# Robot_Psoc_Caras_2_2.net
KiCad netlist of a schematic drawn in EAGLE
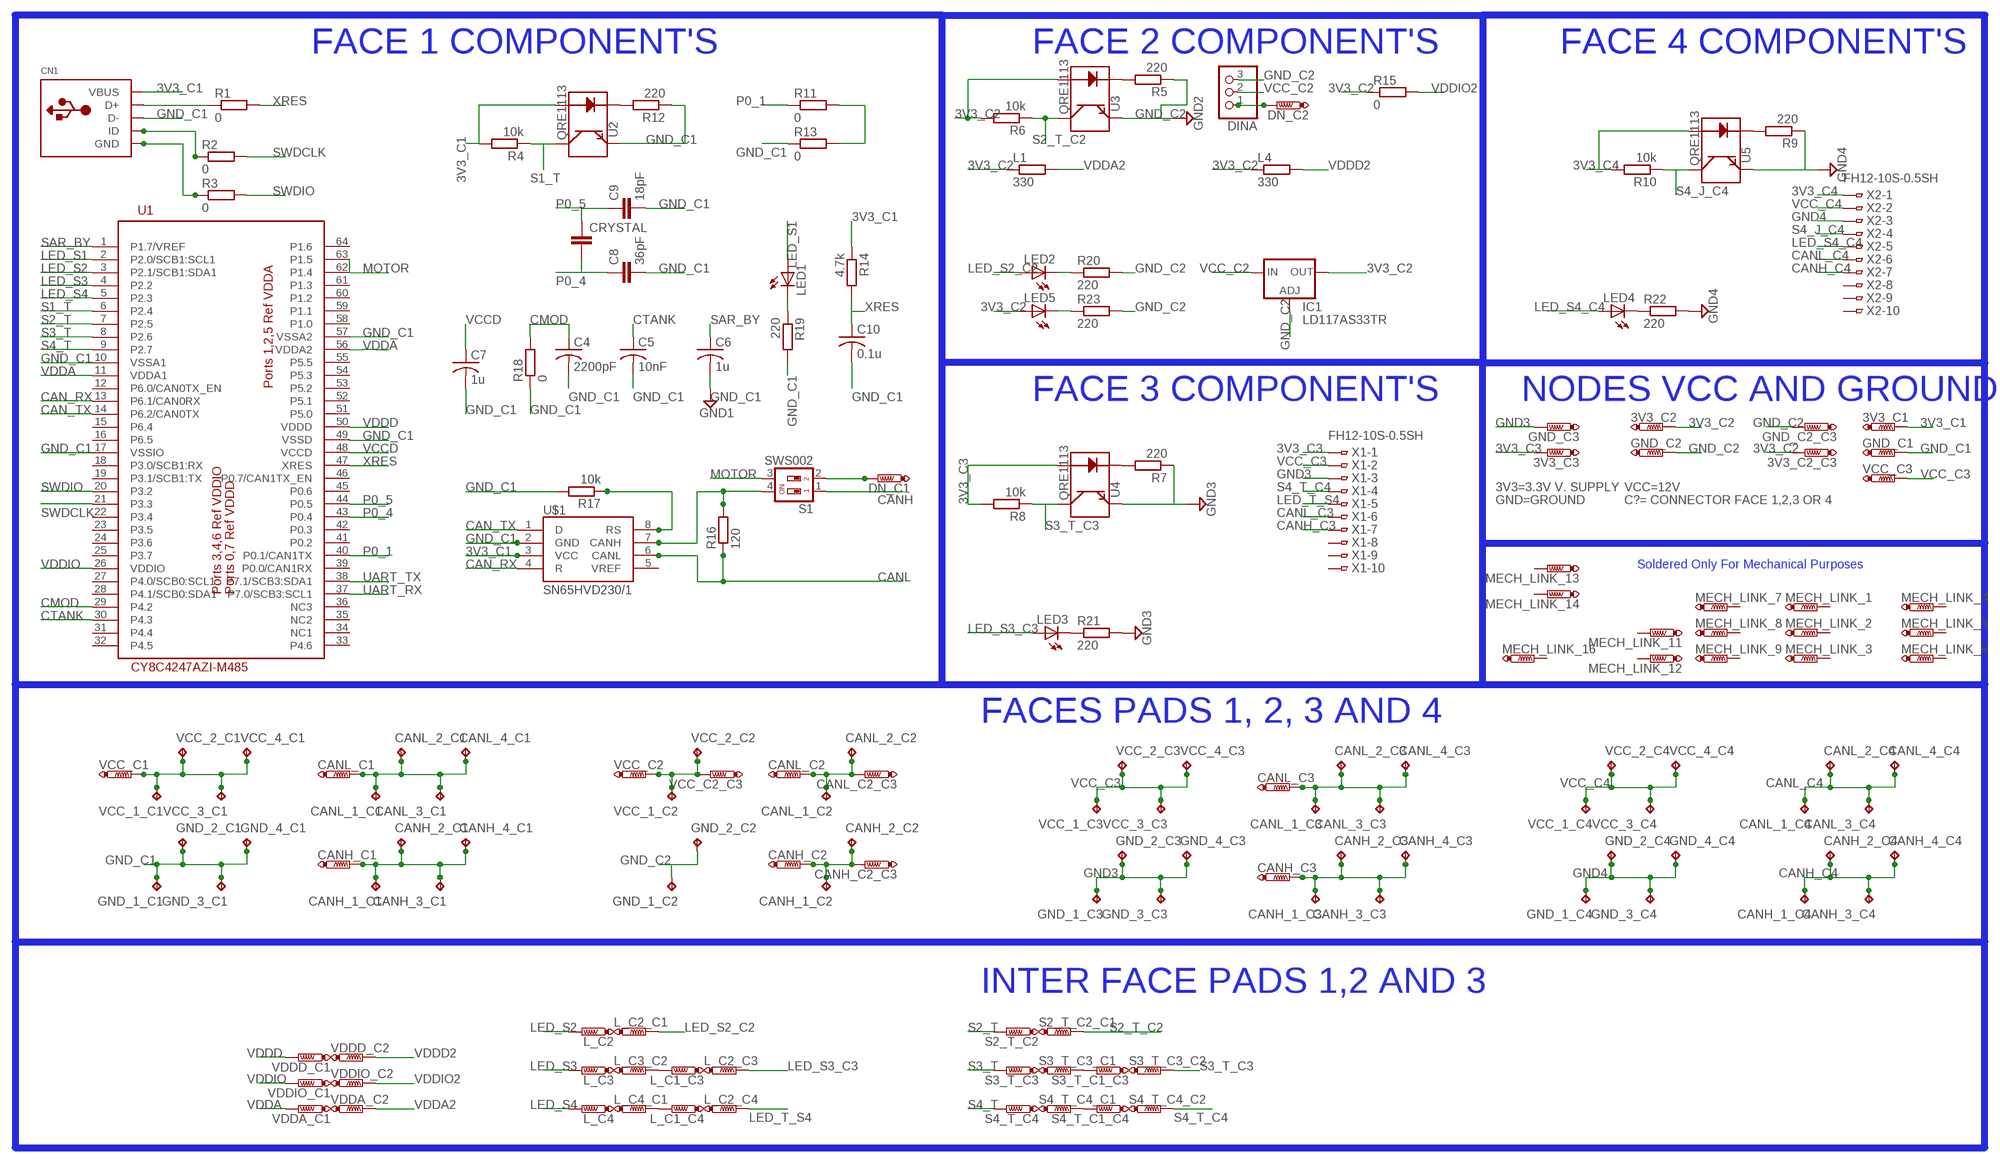
[diagram p0: schematic, sheet 1]

(export (version "E")
  (design (tool "Eeschema 10.0.6"))
  (components
    (comp (ref "3V3_C1")
      (value "PTR1TP11R")
      (footprint "eagle-import:TP11R")
      (libsource (lib "eagle-import") (part "PTR1TP11R"))
    )
    (comp (ref "3V3_C2")
      (value "PTR1TP11R")
      (footprint "eagle-import:TP11R")
      (libsource (lib "eagle-import") (part "PTR1TP11R"))
    )
    (comp (ref "3V3_C2_C3")
      (value "PTR1TP11R")
      (footprint "eagle-import:TP11R")
      (libsource (lib "eagle-import") (part "PTR1TP11R"))
    )
    (comp (ref "3V3_C3")
      (value "PTR1TP11R")
      (footprint "eagle-import:TP11R")
      (libsource (lib "eagle-import") (part "PTR1TP11R"))
    )
    (comp (ref "C4")
      (value "2200pF")
      (footprint "eagle-import:C0805")
      (libsource (lib "eagle-import") (part "C-USC0805"))
    )
    (comp (ref "C5")
      (value "10nF")
      (footprint "eagle-import:C0805")
      (libsource (lib "eagle-import") (part "C-USC0805"))
    )
    (comp (ref "C6")
      (value "1u")
      (footprint "eagle-import:C0805")
      (libsource (lib "eagle-import") (part "C-USC0805"))
    )
    (comp (ref "C7")
      (value "1u")
      (footprint "eagle-import:C0805")
      (libsource (lib "eagle-import") (part "C-USC0805"))
    )
    (comp (ref "C8")
      (value "36pF")
      (footprint "eagle-import:C0805")
      (libsource (lib "eagle-import") (part "C-EUC0805"))
    )
    (comp (ref "C9")
      (value "18pF")
      (footprint "eagle-import:C0805")
      (libsource (lib "eagle-import") (part "C-EUC0805"))
    )
    (comp (ref "C10")
      (value "0.1u")
      (footprint "eagle-import:C0805")
      (libsource (lib "eagle-import") (part "C-USC0805"))
    )
    (comp (ref "CANH_1_C1")
      (value "TPB2,54")
      (footprint "eagle-import:B2,54")
      (libsource (lib "eagle-import") (part "TPB2,54"))
    )
    (comp (ref "CANH_1_C2")
      (value "TPB2,54")
      (footprint "eagle-import:B2,54")
      (libsource (lib "eagle-import") (part "TPB2,54"))
    )
    (comp (ref "CANH_1_C3")
      (value "TPB2,54")
      (footprint "eagle-import:B2,54")
      (libsource (lib "eagle-import") (part "TPB2,54"))
    )
    (comp (ref "CANH_1_C4")
      (value "TPB2,54")
      (footprint "eagle-import:B2,54")
      (libsource (lib "eagle-import") (part "TPB2,54"))
    )
    (comp (ref "CANH_2_C1")
      (value "TPB2,54")
      (footprint "eagle-import:B2,54")
      (libsource (lib "eagle-import") (part "TPB2,54"))
    )
    (comp (ref "CANH_2_C2")
      (value "TPB2,54")
      (footprint "eagle-import:B2,54")
      (libsource (lib "eagle-import") (part "TPB2,54"))
    )
    (comp (ref "CANH_2_C3")
      (value "TPB2,54")
      (footprint "eagle-import:B2,54")
      (libsource (lib "eagle-import") (part "TPB2,54"))
    )
    (comp (ref "CANH_2_C4")
      (value "TPB2,54")
      (footprint "eagle-import:B2,54")
      (libsource (lib "eagle-import") (part "TPB2,54"))
    )
    (comp (ref "CANH_3_C1")
      (value "TPB2,54")
      (footprint "eagle-import:B2,54")
      (libsource (lib "eagle-import") (part "TPB2,54"))
    )
    (comp (ref "CANH_3_C3")
      (value "TPB2,54")
      (footprint "eagle-import:B2,54")
      (libsource (lib "eagle-import") (part "TPB2,54"))
    )
    (comp (ref "CANH_3_C4")
      (value "TPB2,54")
      (footprint "eagle-import:B2,54")
      (libsource (lib "eagle-import") (part "TPB2,54"))
    )
    (comp (ref "CANH_4_C1")
      (value "TPB2,54")
      (footprint "eagle-import:B2,54")
      (libsource (lib "eagle-import") (part "TPB2,54"))
    )
    (comp (ref "CANH_4_C3")
      (value "TPB2,54")
      (footprint "eagle-import:B2,54")
      (libsource (lib "eagle-import") (part "TPB2,54"))
    )
    (comp (ref "CANH_4_C4")
      (value "TPB2,54")
      (footprint "eagle-import:B2,54")
      (libsource (lib "eagle-import") (part "TPB2,54"))
    )
    (comp (ref "CANH_C1")
      (value "PTR1TP11R")
      (footprint "eagle-import:TP11R")
      (libsource (lib "eagle-import") (part "PTR1TP11R"))
    )
    (comp (ref "CANH_C2")
      (value "PTR1TP11R")
      (footprint "eagle-import:TP11R")
      (libsource (lib "eagle-import") (part "PTR1TP11R"))
    )
    (comp (ref "CANH_C2_C3")
      (value "PTR1TP11R")
      (footprint "eagle-import:TP11R")
      (libsource (lib "eagle-import") (part "PTR1TP11R"))
    )
    (comp (ref "CANH_C3")
      (value "PTR1TP11R")
      (footprint "eagle-import:TP11R")
      (libsource (lib "eagle-import") (part "PTR1TP11R"))
    )
    (comp (ref "CANL_1_C1")
      (value "TPB2,54")
      (footprint "eagle-import:B2,54")
      (libsource (lib "eagle-import") (part "TPB2,54"))
    )
    (comp (ref "CANL_1_C2")
      (value "TPB2,54")
      (footprint "eagle-import:B2,54")
      (libsource (lib "eagle-import") (part "TPB2,54"))
    )
    (comp (ref "CANL_1_C3")
      (value "TPB2,54")
      (footprint "eagle-import:B2,54")
      (libsource (lib "eagle-import") (part "TPB2,54"))
    )
    (comp (ref "CANL_1_C4")
      (value "TPB2,54")
      (footprint "eagle-import:B2,54")
      (libsource (lib "eagle-import") (part "TPB2,54"))
    )
    (comp (ref "CANL_2_C1")
      (value "TPB2,54")
      (footprint "eagle-import:B2,54")
      (libsource (lib "eagle-import") (part "TPB2,54"))
    )
    (comp (ref "CANL_2_C2")
      (value "TPB2,54")
      (footprint "eagle-import:B2,54")
      (libsource (lib "eagle-import") (part "TPB2,54"))
    )
    (comp (ref "CANL_2_C3")
      (value "TPB2,54")
      (footprint "eagle-import:B2,54")
      (libsource (lib "eagle-import") (part "TPB2,54"))
    )
    (comp (ref "CANL_2_C4")
      (value "TPB2,54")
      (footprint "eagle-import:B2,54")
      (libsource (lib "eagle-import") (part "TPB2,54"))
    )
    (comp (ref "CANL_3_C1")
      (value "TPB2,54")
      (footprint "eagle-import:B2,54")
      (libsource (lib "eagle-import") (part "TPB2,54"))
    )
    (comp (ref "CANL_3_C3")
      (value "TPB2,54")
      (footprint "eagle-import:B2,54")
      (libsource (lib "eagle-import") (part "TPB2,54"))
    )
    (comp (ref "CANL_3_C4")
      (value "TPB2,54")
      (footprint "eagle-import:B2,54")
      (libsource (lib "eagle-import") (part "TPB2,54"))
    )
    (comp (ref "CANL_4_C1")
      (value "TPB2,54")
      (footprint "eagle-import:B2,54")
      (libsource (lib "eagle-import") (part "TPB2,54"))
    )
    (comp (ref "CANL_4_C3")
      (value "TPB2,54")
      (footprint "eagle-import:B2,54")
      (libsource (lib "eagle-import") (part "TPB2,54"))
    )
    (comp (ref "CANL_4_C4")
      (value "TPB2,54")
      (footprint "eagle-import:B2,54")
      (libsource (lib "eagle-import") (part "TPB2,54"))
    )
    (comp (ref "CANL_C1")
      (value "PTR1TP11R")
      (footprint "eagle-import:TP11R")
      (libsource (lib "eagle-import") (part "PTR1TP11R"))
    )
    (comp (ref "CANL_C2")
      (value "PTR1TP11R")
      (footprint "eagle-import:TP11R")
      (libsource (lib "eagle-import") (part "PTR1TP11R"))
    )
    (comp (ref "CANL_C2_C3")
      (value "PTR1TP11R")
      (footprint "eagle-import:TP11R")
      (libsource (lib "eagle-import") (part "PTR1TP11R"))
    )
    (comp (ref "CANL_C3")
      (value "PTR1TP11R")
      (footprint "eagle-import:TP11R")
      (libsource (lib "eagle-import") (part "PTR1TP11R"))
    )
    (comp (ref "CN1")
      (value "USBMINIB")
      (footprint "eagle-import:USB-MINIB")
      (libsource (lib "eagle-import") (part "USBMINIB"))
    )
    (comp (ref "CRYSTAL")
      (value "C-EUC0603")
      (footprint "eagle-import:C0603")
      (libsource (lib "eagle-import") (part "C-EUC0603"))
    )
    (comp (ref "DINA")
      (value "PINHD-1X3")
      (footprint "eagle-import:1X03")
      (libsource (lib "eagle-import") (part "PINHD-1X3"))
    )
    (comp (ref "DN_C1")
      (value "PTR1TP11R")
      (footprint "eagle-import:TP11R")
      (libsource (lib "eagle-import") (part "PTR1TP11R"))
    )
    (comp (ref "DN_C2")
      (value "PTR1TP11R")
      (footprint "eagle-import:TP11R")
      (libsource (lib "eagle-import") (part "PTR1TP11R"))
    )
    (comp (ref "GND_1_C1")
      (value "TPB2,54")
      (footprint "eagle-import:B2,54")
      (libsource (lib "eagle-import") (part "TPB2,54"))
    )
    (comp (ref "GND_1_C2")
      (value "TPB2,54")
      (footprint "eagle-import:B2,54")
      (libsource (lib "eagle-import") (part "TPB2,54"))
    )
    (comp (ref "GND_1_C3")
      (value "TPB2,54")
      (footprint "eagle-import:B2,54")
      (libsource (lib "eagle-import") (part "TPB2,54"))
    )
    (comp (ref "GND_1_C4")
      (value "TPB2,54")
      (footprint "eagle-import:B2,54")
      (libsource (lib "eagle-import") (part "TPB2,54"))
    )
    (comp (ref "GND_2_C1")
      (value "TPB2,54")
      (footprint "eagle-import:B2,54")
      (libsource (lib "eagle-import") (part "TPB2,54"))
    )
    (comp (ref "GND_2_C2")
      (value "TPB2,54")
      (footprint "eagle-import:B2,54")
      (libsource (lib "eagle-import") (part "TPB2,54"))
    )
    (comp (ref "GND_2_C3")
      (value "TPB2,54")
      (footprint "eagle-import:B2,54")
      (libsource (lib "eagle-import") (part "TPB2,54"))
    )
    (comp (ref "GND_2_C4")
      (value "TPB2,54")
      (footprint "eagle-import:B2,54")
      (libsource (lib "eagle-import") (part "TPB2,54"))
    )
    (comp (ref "GND_3_C1")
      (value "TPB2,54")
      (footprint "eagle-import:B2,54")
      (libsource (lib "eagle-import") (part "TPB2,54"))
    )
    (comp (ref "GND_3_C3")
      (value "TPB2,54")
      (footprint "eagle-import:B2,54")
      (libsource (lib "eagle-import") (part "TPB2,54"))
    )
    (comp (ref "GND_3_C4")
      (value "TPB2,54")
      (footprint "eagle-import:B2,54")
      (libsource (lib "eagle-import") (part "TPB2,54"))
    )
    (comp (ref "GND_4_C1")
      (value "TPB2,54")
      (footprint "eagle-import:B2,54")
      (libsource (lib "eagle-import") (part "TPB2,54"))
    )
    (comp (ref "GND_4_C3")
      (value "TPB2,54")
      (footprint "eagle-import:B2,54")
      (libsource (lib "eagle-import") (part "TPB2,54"))
    )
    (comp (ref "GND_4_C4")
      (value "TPB2,54")
      (footprint "eagle-import:B2,54")
      (libsource (lib "eagle-import") (part "TPB2,54"))
    )
    (comp (ref "GND_C1")
      (value "PTR1TP11R")
      (footprint "eagle-import:TP11R")
      (libsource (lib "eagle-import") (part "PTR1TP11R"))
    )
    (comp (ref "GND_C2")
      (value "PTR1TP11R")
      (footprint "eagle-import:TP11R")
      (libsource (lib "eagle-import") (part "PTR1TP11R"))
    )
    (comp (ref "GND_C2_C3")
      (value "PTR1TP11R")
      (footprint "eagle-import:TP11R")
      (libsource (lib "eagle-import") (part "PTR1TP11R"))
    )
    (comp (ref "GND_C3")
      (value "PTR1TP11R")
      (footprint "eagle-import:TP11R")
      (libsource (lib "eagle-import") (part "PTR1TP11R"))
    )
    (comp (ref "IC1")
      (value "LD117AS33TR")
      (footprint "eagle-import:SOT223")
      (libsource (lib "eagle-import") (part "LD117A?S33TR"))
    )
    (comp (ref "L1")
      (value "330")
      (footprint "eagle-import:R0805")
      (libsource (lib "eagle-import") (part "R-EU_R0805"))
    )
    (comp (ref "L4")
      (value "330")
      (footprint "eagle-import:R0805")
      (libsource (lib "eagle-import") (part "R-EU_R0805"))
    )
    (comp (ref "LED1")
      (value "LEDCHIPLED_0805")
      (footprint "eagle-import:CHIPLED_0805")
      (libsource (lib "eagle-import") (part "LEDCHIPLED_0805"))
    )
    (comp (ref "LED2")
      (value "LEDCHIPLED_0805")
      (footprint "eagle-import:CHIPLED_0805")
      (libsource (lib "eagle-import") (part "LEDCHIPLED_0805"))
    )
    (comp (ref "LED3")
      (value "LEDCHIPLED_0805")
      (footprint "eagle-import:CHIPLED_0805")
      (libsource (lib "eagle-import") (part "LEDCHIPLED_0805"))
    )
    (comp (ref "LED4")
      (value "LEDCHIPLED_0805")
      (footprint "eagle-import:CHIPLED_0805")
      (libsource (lib "eagle-import") (part "LEDCHIPLED_0805"))
    )
    (comp (ref "LED5")
      (value "LEDCHIPLED_0805")
      (footprint "eagle-import:CHIPLED_0805")
      (libsource (lib "eagle-import") (part "LEDCHIPLED_0805"))
    )
    (comp (ref "L_C1_C3")
      (value "PTR1TP11R")
      (footprint "eagle-import:TP11R")
      (libsource (lib "eagle-import") (part "PTR1TP11R"))
    )
    (comp (ref "L_C1_C4")
      (value "PTR1TP11R")
      (footprint "eagle-import:TP11R")
      (libsource (lib "eagle-import") (part "PTR1TP11R"))
    )
    (comp (ref "L_C2")
      (value "PTR1TP11R")
      (footprint "eagle-import:TP11R")
      (libsource (lib "eagle-import") (part "PTR1TP11R"))
    )
    (comp (ref "L_C2_C1")
      (value "PTR1TP11R")
      (footprint "eagle-import:TP11R")
      (libsource (lib "eagle-import") (part "PTR1TP11R"))
    )
    (comp (ref "L_C2_C3")
      (value "PTR1TP11R")
      (footprint "eagle-import:TP11R")
      (libsource (lib "eagle-import") (part "PTR1TP11R"))
    )
    (comp (ref "L_C2_C4")
      (value "PTR1TP11R")
      (footprint "eagle-import:TP11R")
      (libsource (lib "eagle-import") (part "PTR1TP11R"))
    )
    (comp (ref "L_C3")
      (value "PTR1TP11R")
      (footprint "eagle-import:TP11R")
      (libsource (lib "eagle-import") (part "PTR1TP11R"))
    )
    (comp (ref "L_C3_C2")
      (value "PTR1TP11R")
      (footprint "eagle-import:TP11R")
      (libsource (lib "eagle-import") (part "PTR1TP11R"))
    )
    (comp (ref "L_C4")
      (value "PTR1TP11R")
      (footprint "eagle-import:TP11R")
      (libsource (lib "eagle-import") (part "PTR1TP11R"))
    )
    (comp (ref "L_C4_C1")
      (value "PTR1TP11R")
      (footprint "eagle-import:TP11R")
      (libsource (lib "eagle-import") (part "PTR1TP11R"))
    )
    (comp (ref "MECH_LINK_1")
      (value "PTR1TP11R")
      (footprint "eagle-import:TP11R")
      (libsource (lib "eagle-import") (part "PTR1TP11R"))
    )
    (comp (ref "MECH_LINK_2")
      (value "PTR1TP11R")
      (footprint "eagle-import:TP11R")
      (libsource (lib "eagle-import") (part "PTR1TP11R"))
    )
    (comp (ref "MECH_LINK_3")
      (value "PTR1TP11R")
      (footprint "eagle-import:TP11R")
      (libsource (lib "eagle-import") (part "PTR1TP11R"))
    )
    (comp (ref "MECH_LINK_4")
      (value "PTR1TP11R")
      (footprint "eagle-import:TP11R")
      (libsource (lib "eagle-import") (part "PTR1TP11R"))
    )
    (comp (ref "MECH_LINK_5")
      (value "PTR1TP11R")
      (footprint "eagle-import:TP11R")
      (libsource (lib "eagle-import") (part "PTR1TP11R"))
    )
    (comp (ref "MECH_LINK_6")
      (value "PTR1TP11R")
      (footprint "eagle-import:TP11R")
      (libsource (lib "eagle-import") (part "PTR1TP11R"))
    )
    (comp (ref "MECH_LINK_7")
      (value "PTR1TP11R")
      (footprint "eagle-import:TP11R")
      (libsource (lib "eagle-import") (part "PTR1TP11R"))
    )
    (comp (ref "MECH_LINK_8")
      (value "PTR1TP11R")
      (footprint "eagle-import:TP11R")
      (libsource (lib "eagle-import") (part "PTR1TP11R"))
    )
    (comp (ref "MECH_LINK_9")
      (value "PTR1TP11R")
      (footprint "eagle-import:TP11R")
      (libsource (lib "eagle-import") (part "PTR1TP11R"))
    )
    (comp (ref "MECH_LINK_11")
      (value "PTR1TP11R")
      (footprint "eagle-import:TP11R")
      (libsource (lib "eagle-import") (part "PTR1TP11R"))
    )
    (comp (ref "MECH_LINK_12")
      (value "PTR1TP11R")
      (footprint "eagle-import:TP11R")
      (libsource (lib "eagle-import") (part "PTR1TP11R"))
    )
    (comp (ref "MECH_LINK_13")
      (value "PTR1TP11R")
      (footprint "eagle-import:TP11R")
      (libsource (lib "eagle-import") (part "PTR1TP11R"))
    )
    (comp (ref "MECH_LINK_14")
      (value "PTR1TP11R")
      (footprint "eagle-import:TP11R")
      (libsource (lib "eagle-import") (part "PTR1TP11R"))
    )
    (comp (ref "MECH_LINK_16")
      (value "PTR1TP11R")
      (footprint "eagle-import:TP11R")
      (libsource (lib "eagle-import") (part "PTR1TP11R"))
    )
    (comp (ref "R1")
      (value "0")
      (footprint "eagle-import:R0805")
      (libsource (lib "eagle-import") (part "R-EU_R0805"))
    )
    (comp (ref "R2")
      (value "0")
      (footprint "eagle-import:R0805")
      (libsource (lib "eagle-import") (part "R-EU_R0805"))
    )
    (comp (ref "R3")
      (value "0")
      (footprint "eagle-import:R0805")
      (libsource (lib "eagle-import") (part "R-EU_R0805"))
    )
    (comp (ref "R4")
      (value "10k")
      (footprint "eagle-import:R0805")
      (libsource (lib "eagle-import") (part "R-EU_R0805"))
    )
    (comp (ref "R5")
      (value "220")
      (footprint "eagle-import:R0805")
      (libsource (lib "eagle-import") (part "R-EU_R0805"))
    )
    (comp (ref "R6")
      (value "10k")
      (footprint "eagle-import:R0805")
      (libsource (lib "eagle-import") (part "R-EU_R0805"))
    )
    (comp (ref "R7")
      (value "220")
      (footprint "eagle-import:R0805")
      (libsource (lib "eagle-import") (part "R-EU_R0805"))
    )
    (comp (ref "R8")
      (value "10k")
      (footprint "eagle-import:R0805")
      (libsource (lib "eagle-import") (part "R-EU_R0805"))
    )
    (comp (ref "R9")
      (value "220")
      (footprint "eagle-import:R0805")
      (libsource (lib "eagle-import") (part "R-EU_R0805"))
    )
    (comp (ref "R10")
      (value "10k")
      (footprint "eagle-import:R0805")
      (libsource (lib "eagle-import") (part "R-EU_R0805"))
    )
    (comp (ref "R11")
      (value "0")
      (footprint "eagle-import:R0805")
      (libsource (lib "eagle-import") (part "R-EU_R0805"))
    )
    (comp (ref "R12")
      (value "220")
      (footprint "eagle-import:R0805")
      (libsource (lib "eagle-import") (part "R-EU_R0805"))
    )
    (comp (ref "R13")
      (value "0")
      (footprint "eagle-import:R0805")
      (libsource (lib "eagle-import") (part "R-EU_R0805"))
    )
    (comp (ref "R14")
      (value "4.7k")
      (footprint "eagle-import:R0805")
      (libsource (lib "eagle-import") (part "R-EU_R0805"))
    )
    (comp (ref "R15")
      (value "0")
      (footprint "eagle-import:R0805")
      (libsource (lib "eagle-import") (part "R-EU_R0805"))
    )
    (comp (ref "R16")
      (value "120")
      (footprint "eagle-import:R0805")
      (libsource (lib "eagle-import") (part "R-EU_R0805"))
    )
    (comp (ref "R17")
      (value "10k")
      (footprint "eagle-import:R0805")
      (libsource (lib "eagle-import") (part "R-EU_R0805"))
    )
    (comp (ref "R18")
      (value "0")
      (footprint "eagle-import:R0805")
      (libsource (lib "eagle-import") (part "R-EU_R0805"))
    )
    (comp (ref "R19")
      (value "220")
      (footprint "eagle-import:R0805")
      (libsource (lib "eagle-import") (part "R-EU_R0805"))
    )
    (comp (ref "R20")
      (value "220")
      (footprint "eagle-import:R0805")
      (libsource (lib "eagle-import") (part "R-EU_R0805"))
    )
    (comp (ref "R21")
      (value "220")
      (footprint "eagle-import:R0805")
      (libsource (lib "eagle-import") (part "R-EU_R0805"))
    )
    (comp (ref "R22")
      (value "220")
      (footprint "eagle-import:R0805")
      (libsource (lib "eagle-import") (part "R-EU_R0805"))
    )
    (comp (ref "R23")
      (value "220")
      (footprint "eagle-import:R0805")
      (libsource (lib "eagle-import") (part "R-EU_R0805"))
    )
    (comp (ref "S1")
      (value "SWS002")
      (footprint "eagle-import:SMS-002")
      (libsource (lib "eagle-import") (part "SWS002"))
    )
    (comp (ref "S2_T_C2")
      (value "PTR1TP11R")
      (footprint "eagle-import:TP11R")
      (libsource (lib "eagle-import") (part "PTR1TP11R"))
    )
    (comp (ref "S2_T_C2_C1")
      (value "PTR1TP11R")
      (footprint "eagle-import:TP11R")
      (libsource (lib "eagle-import") (part "PTR1TP11R"))
    )
    (comp (ref "S3_T_C1_C3")
      (value "PTR1TP11R")
      (footprint "eagle-import:TP11R")
      (libsource (lib "eagle-import") (part "PTR1TP11R"))
    )
    (comp (ref "S3_T_C3")
      (value "PTR1TP11R")
      (footprint "eagle-import:TP11R")
      (libsource (lib "eagle-import") (part "PTR1TP11R"))
    )
    (comp (ref "S3_T_C3_C1")
      (value "PTR1TP11R")
      (footprint "eagle-import:TP11R")
      (libsource (lib "eagle-import") (part "PTR1TP11R"))
    )
    (comp (ref "S3_T_C3_C2")
      (value "PTR1TP11R")
      (footprint "eagle-import:TP11R")
      (libsource (lib "eagle-import") (part "PTR1TP11R"))
    )
    (comp (ref "S4_T_C1_C4")
      (value "PTR1TP11R")
      (footprint "eagle-import:TP11R")
      (libsource (lib "eagle-import") (part "PTR1TP11R"))
    )
    (comp (ref "S4_T_C4")
      (value "PTR1TP11R")
      (footprint "eagle-import:TP11R")
      (libsource (lib "eagle-import") (part "PTR1TP11R"))
    )
    (comp (ref "S4_T_C4_C1")
      (value "PTR1TP11R")
      (footprint "eagle-import:TP11R")
      (libsource (lib "eagle-import") (part "PTR1TP11R"))
    )
    (comp (ref "S4_T_C4_C2")
      (value "PTR1TP11R")
      (footprint "eagle-import:TP11R")
      (libsource (lib "eagle-import") (part "PTR1TP11R"))
    )
    (comp (ref "U$1")
      (value "SN65HVD230/1")
      (footprint "eagle-import:SO8")
      (libsource (lib "eagle-import") (part "SN65HVD230/1"))
    )
    (comp (ref "U1")
      (value "CY8C4247AZI-M485")
      (footprint "eagle-import:TQFP64-10X10")
      (libsource (lib "eagle-import") (part "CY8C4247AZI-M485"))
    )
    (comp (ref "U2")
      (value "QRE1113")
      (footprint "eagle-import:QRE1113")
      (libsource (lib "eagle-import") (part "QRE1113"))
    )
    (comp (ref "U3")
      (value "QRE1113")
      (footprint "eagle-import:QRE1113")
      (libsource (lib "eagle-import") (part "QRE1113"))
    )
    (comp (ref "U4")
      (value "QRE1113")
      (footprint "eagle-import:QRE1113")
      (libsource (lib "eagle-import") (part "QRE1113"))
    )
    (comp (ref "U5")
      (value "QRE1113")
      (footprint "eagle-import:QRE1113")
      (libsource (lib "eagle-import") (part "QRE1113"))
    )
    (comp (ref "VCC_1_C1")
      (value "TPB2,54")
      (footprint "eagle-import:B2,54")
      (libsource (lib "eagle-import") (part "TPB2,54"))
    )
    (comp (ref "VCC_1_C2")
      (value "TPB2,54")
      (footprint "eagle-import:B2,54")
      (libsource (lib "eagle-import") (part "TPB2,54"))
    )
    (comp (ref "VCC_1_C3")
      (value "TPB2,54")
      (footprint "eagle-import:B2,54")
      (libsource (lib "eagle-import") (part "TPB2,54"))
    )
    (comp (ref "VCC_1_C4")
      (value "TPB2,54")
      (footprint "eagle-import:B2,54")
      (libsource (lib "eagle-import") (part "TPB2,54"))
    )
    (comp (ref "VCC_2_C1")
      (value "TPB2,54")
      (footprint "eagle-import:B2,54")
      (libsource (lib "eagle-import") (part "TPB2,54"))
    )
    (comp (ref "VCC_2_C2")
      (value "TPB2,54")
      (footprint "eagle-import:B2,54")
      (libsource (lib "eagle-import") (part "TPB2,54"))
    )
    (comp (ref "VCC_2_C3")
      (value "TPB2,54")
      (footprint "eagle-import:B2,54")
      (libsource (lib "eagle-import") (part "TPB2,54"))
    )
    (comp (ref "VCC_2_C4")
      (value "TPB2,54")
      (footprint "eagle-import:B2,54")
      (libsource (lib "eagle-import") (part "TPB2,54"))
    )
    (comp (ref "VCC_3_C1")
      (value "TPB2,54")
      (footprint "eagle-import:B2,54")
      (libsource (lib "eagle-import") (part "TPB2,54"))
    )
    (comp (ref "VCC_3_C3")
      (value "TPB2,54")
      (footprint "eagle-import:B2,54")
      (libsource (lib "eagle-import") (part "TPB2,54"))
    )
    (comp (ref "VCC_3_C4")
      (value "TPB2,54")
      (footprint "eagle-import:B2,54")
      (libsource (lib "eagle-import") (part "TPB2,54"))
    )
    (comp (ref "VCC_4_C1")
      (value "TPB2,54")
      (footprint "eagle-import:B2,54")
      (libsource (lib "eagle-import") (part "TPB2,54"))
    )
    (comp (ref "VCC_4_C3")
      (value "TPB2,54")
      (footprint "eagle-import:B2,54")
      (libsource (lib "eagle-import") (part "TPB2,54"))
    )
    (comp (ref "VCC_4_C4")
      (value "TPB2,54")
      (footprint "eagle-import:B2,54")
      (libsource (lib "eagle-import") (part "TPB2,54"))
    )
    (comp (ref "VCC_C1")
      (value "PTR1TP11R")
      (footprint "eagle-import:TP11R")
      (libsource (lib "eagle-import") (part "PTR1TP11R"))
    )
    (comp (ref "VCC_C2")
      (value "PTR1TP11R")
      (footprint "eagle-import:TP11R")
      (libsource (lib "eagle-import") (part "PTR1TP11R"))
    )
    (comp (ref "VCC_C2_C3")
      (value "PTR1TP11R")
      (footprint "eagle-import:TP11R")
      (libsource (lib "eagle-import") (part "PTR1TP11R"))
    )
    (comp (ref "VCC_C3")
      (value "PTR1TP11R")
      (footprint "eagle-import:TP11R")
      (libsource (lib "eagle-import") (part "PTR1TP11R"))
    )
    (comp (ref "VDDA_C1")
      (value "PTR1TP11R")
      (footprint "eagle-import:TP11R")
      (libsource (lib "eagle-import") (part "PTR1TP11R"))
    )
    (comp (ref "VDDA_C2")
      (value "PTR1TP11R")
      (footprint "eagle-import:TP11R")
      (libsource (lib "eagle-import") (part "PTR1TP11R"))
    )
    (comp (ref "VDDD_C1")
      (value "PTR1TP11R")
      (footprint "eagle-import:TP11R")
      (libsource (lib "eagle-import") (part "PTR1TP11R"))
    )
    (comp (ref "VDDD_C2")
      (value "PTR1TP11R")
      (footprint "eagle-import:TP11R")
      (libsource (lib "eagle-import") (part "PTR1TP11R"))
    )
    (comp (ref "VDDIO_C1")
      (value "PTR1TP11R")
      (footprint "eagle-import:TP11R")
      (libsource (lib "eagle-import") (part "PTR1TP11R"))
    )
    (comp (ref "VDDIO_C2")
      (value "PTR1TP11R")
      (footprint "eagle-import:TP11R")
      (libsource (lib "eagle-import") (part "PTR1TP11R"))
    )
    (comp (ref "X1")
      (value "FH12-10S-0.5SH")
      (footprint "eagle-import:FH12-10S-0.5SH")
      (fields (field (name "MPN") "FH12-10S-0.5SH(55)"))
      (libsource (lib "eagle-import") (part "FH12-10S-0.5SH"))
    )
    (comp (ref "X2")
      (value "FH12-10S-0.5SH")
      (footprint "eagle-import:FH12-10S-0.5SH")
      (fields (field (name "MPN") "FH12-10S-0.5SH(55)"))
      (libsource (lib "eagle-import") (part "FH12-10S-0.5SH"))
    )
  )
  (nets
    (net (code "1") (name "/3V3_C1") (class "Default")
      (node (ref "3V3_C1") (pin "TP") (pinfunction "TP_TP") (pintype "input"))
      (node (ref "CN1") (pin "VBUS") (pinfunction "VBUS_VBUS") (pintype "power_in"))
      (node (ref "R14") (pin "1") (pinfunction "1_1") (pintype "passive"))
      (node (ref "R4") (pin "2") (pinfunction "2_2") (pintype "passive"))
      (node (ref "U$1") (pin "3") (pinfunction "VCC_3") (pintype "power_in"))
      (node (ref "U2") (pin "1") (pinfunction "A_1") (pintype "bidirectional"))
    )
    (net (code "2") (name "/3V3_C2") (class "Default")
      (node (ref "3V3_C2") (pin "TP") (pinfunction "TP_TP") (pintype "input"))
      (node (ref "3V3_C2_C3") (pin "TP") (pinfunction "TP_TP") (pintype "input"))
      (node (ref "IC1") (pin "4") (pinfunction "OUT_4") (pintype "passive"))
      (node (ref "L1") (pin "1") (pinfunction "1_1") (pintype "passive"))
      (node (ref "L4") (pin "1") (pinfunction "1_1") (pintype "passive"))
      (node (ref "LED5") (pin "A") (pinfunction "A_A") (pintype "passive"))
      (node (ref "R15") (pin "1") (pinfunction "1_1") (pintype "passive"))
      (node (ref "R6") (pin "2") (pinfunction "2_2") (pintype "passive"))
      (node (ref "U3") (pin "1") (pinfunction "A_1") (pintype "bidirectional"))
    )
    (net (code "3") (name "/3V3_C3") (class "Default")
      (node (ref "3V3_C3") (pin "TP") (pinfunction "TP_TP") (pintype "input"))
      (node (ref "R8") (pin "2") (pinfunction "2_2") (pintype "passive"))
      (node (ref "U4") (pin "1") (pinfunction "A_1") (pintype "bidirectional"))
      (node (ref "X1") (pin "1") (pinfunction "1_1") (pintype "passive"))
    )
    (net (code "4") (name "/3V3_C4") (class "Default")
      (node (ref "R10") (pin "2") (pinfunction "2_2") (pintype "passive"))
      (node (ref "U5") (pin "1") (pinfunction "A_1") (pintype "bidirectional"))
      (node (ref "X2") (pin "1") (pinfunction "1_1") (pintype "passive"))
    )
    (net (code "5") (name "/CANH") (class "Default")
      (node (ref "CANH_1_C1") (pin "TP") (pinfunction "TP_TP") (pintype "input"))
      (node (ref "CANH_2_C1") (pin "TP") (pinfunction "TP_TP") (pintype "input"))
      (node (ref "CANH_3_C1") (pin "TP") (pinfunction "TP_TP") (pintype "input"))
      (node (ref "CANH_4_C1") (pin "TP") (pinfunction "TP_TP") (pintype "input"))
      (node (ref "CANH_C1") (pin "TP") (pinfunction "TP_TP") (pintype "input"))
      (node (ref "S1") (pin "1") (pinfunction "1_1") (pintype "passive"))
    )
    (net (code "6") (name "/CANH_C3") (class "Default")
      (node (ref "CANH_1_C3") (pin "TP") (pinfunction "TP_TP") (pintype "input"))
      (node (ref "CANH_2_C3") (pin "TP") (pinfunction "TP_TP") (pintype "input"))
      (node (ref "CANH_3_C3") (pin "TP") (pinfunction "TP_TP") (pintype "input"))
      (node (ref "CANH_4_C3") (pin "TP") (pinfunction "TP_TP") (pintype "input"))
      (node (ref "CANH_C3") (pin "TP") (pinfunction "TP_TP") (pintype "input"))
      (node (ref "X1") (pin "7") (pinfunction "1_7") (pintype "passive"))
    )
    (net (code "7") (name "/CANH_C4") (class "Default")
      (node (ref "CANH_1_C4") (pin "TP") (pinfunction "TP_TP") (pintype "input"))
      (node (ref "CANH_2_C4") (pin "TP") (pinfunction "TP_TP") (pintype "input"))
      (node (ref "CANH_3_C4") (pin "TP") (pinfunction "TP_TP") (pintype "input"))
      (node (ref "CANH_4_C4") (pin "TP") (pinfunction "TP_TP") (pintype "input"))
      (node (ref "X2") (pin "7") (pinfunction "1_7") (pintype "passive"))
    )
    (net (code "8") (name "/CANL") (class "Default")
      (node (ref "CANL_1_C1") (pin "TP") (pinfunction "TP_TP") (pintype "input"))
      (node (ref "CANL_2_C1") (pin "TP") (pinfunction "TP_TP") (pintype "input"))
      (node (ref "CANL_3_C1") (pin "TP") (pinfunction "TP_TP") (pintype "input"))
      (node (ref "CANL_4_C1") (pin "TP") (pinfunction "TP_TP") (pintype "input"))
      (node (ref "CANL_C1") (pin "TP") (pinfunction "TP_TP") (pintype "input"))
      (node (ref "R16") (pin "1") (pinfunction "1_1") (pintype "passive"))
      (node (ref "U$1") (pin "6") (pinfunction "CANL_6") (pintype "bidirectional"))
    )
    (net (code "9") (name "/CANL_C3") (class "Default")
      (node (ref "CANL_1_C3") (pin "TP") (pinfunction "TP_TP") (pintype "input"))
      (node (ref "CANL_2_C3") (pin "TP") (pinfunction "TP_TP") (pintype "input"))
      (node (ref "CANL_3_C3") (pin "TP") (pinfunction "TP_TP") (pintype "input"))
      (node (ref "CANL_4_C3") (pin "TP") (pinfunction "TP_TP") (pintype "input"))
      (node (ref "CANL_C3") (pin "TP") (pinfunction "TP_TP") (pintype "input"))
      (node (ref "X1") (pin "6") (pinfunction "1_6") (pintype "passive"))
    )
    (net (code "10") (name "/CANL_C4") (class "Default")
      (node (ref "CANL_1_C4") (pin "TP") (pinfunction "TP_TP") (pintype "input"))
      (node (ref "CANL_2_C4") (pin "TP") (pinfunction "TP_TP") (pintype "input"))
      (node (ref "CANL_3_C4") (pin "TP") (pinfunction "TP_TP") (pintype "input"))
      (node (ref "CANL_4_C4") (pin "TP") (pinfunction "TP_TP") (pintype "input"))
      (node (ref "X2") (pin "6") (pinfunction "1_6") (pintype "passive"))
    )
    (net (code "11") (name "/CAN_RX") (class "Default")
      (node (ref "U$1") (pin "4") (pinfunction "R_4") (pintype "bidirectional"))
      (node (ref "U1") (pin "13") (pinfunction "P6.1/CAN0RX_13") (pintype "bidirectional"))
    )
    (net (code "12") (name "/CAN_TX") (class "Default")
      (node (ref "U$1") (pin "1") (pinfunction "D_1") (pintype "bidirectional"))
      (node (ref "U1") (pin "14") (pinfunction "P6.2/CAN0TX_14") (pintype "bidirectional"))
    )
    (net (code "13") (name "/CMOD") (class "Default")
      (node (ref "C4") (pin "1") (pinfunction "1_1") (pintype "passive"))
      (node (ref "R18") (pin "2") (pinfunction "2_2") (pintype "passive"))
      (node (ref "U1") (pin "29") (pinfunction "P4.2_29") (pintype "bidirectional"))
    )
    (net (code "14") (name "/CTANK") (class "Default")
      (node (ref "C5") (pin "1") (pinfunction "1_1") (pintype "passive"))
      (node (ref "U1") (pin "30") (pinfunction "P4.3_30") (pintype "bidirectional"))
    )
    (net (code "15") (name "/LED_S1") (class "Default")
      (node (ref "LED1") (pin "A") (pinfunction "A_A") (pintype "passive"))
      (node (ref "U1") (pin "2") (pinfunction "P2.0/SCB1:SCL1_2") (pintype "bidirectional"))
    )
    (net (code "16") (name "/LED_S2") (class "Default")
      (node (ref "L_C2") (pin "TP") (pinfunction "TP_TP") (pintype "input"))
      (node (ref "U1") (pin "3") (pinfunction "P2.1/SCB1:SDA1_3") (pintype "bidirectional"))
    )
    (net (code "17") (name "/LED_S2_C2") (class "Default")
      (node (ref "LED2") (pin "A") (pinfunction "A_A") (pintype "passive"))
      (node (ref "L_C2_C1") (pin "TP") (pinfunction "TP_TP") (pintype "input"))
    )
    (net (code "18") (name "/LED_S3") (class "Default")
      (node (ref "L_C3") (pin "TP") (pinfunction "TP_TP") (pintype "input"))
      (node (ref "U1") (pin "4") (pinfunction "P2.2_4") (pintype "bidirectional"))
    )
    (net (code "19") (name "/LED_S3_C3") (class "Default")
      (node (ref "LED3") (pin "A") (pinfunction "A_A") (pintype "passive"))
      (node (ref "L_C2_C3") (pin "TP") (pinfunction "TP_TP") (pintype "input"))
    )
    (net (code "20") (name "/LED_S4") (class "Default")
      (node (ref "L_C4") (pin "TP") (pinfunction "TP_TP") (pintype "input"))
      (node (ref "U1") (pin "5") (pinfunction "P2.3_5") (pintype "bidirectional"))
    )
    (net (code "21") (name "/LED_S4_C4") (class "Default")
      (node (ref "LED4") (pin "A") (pinfunction "A_A") (pintype "passive"))
      (node (ref "X2") (pin "5") (pinfunction "1_5") (pintype "passive"))
    )
    (net (code "22") (name "/LED_T_S4") (class "Default")
      (node (ref "L_C2_C4") (pin "TP") (pinfunction "TP_TP") (pintype "input"))
      (node (ref "X1") (pin "5") (pinfunction "1_5") (pintype "passive"))
    )
    (net (code "23") (name "/MOTOR") (class "Default")
      (node (ref "S1") (pin "3") (pinfunction "3_3") (pintype "passive"))
      (node (ref "U1") (pin "62") (pinfunction "P1.4_62") (pintype "bidirectional"))
      (node (ref "U1") (pin "63") (pinfunction "P1.5_63") (pintype "bidirectional"))
    )
    (net (code "24") (name "/P0_1") (class "Default")
      (node (ref "R11") (pin "1") (pinfunction "1_1") (pintype "passive"))
      (node (ref "U1") (pin "40") (pinfunction "P0.1/CAN1TX_40") (pintype "bidirectional"))
    )
    (net (code "25") (name "/P0_4") (class "Default")
      (node (ref "C8") (pin "1") (pinfunction "1_1") (pintype "passive"))
      (node (ref "CRYSTAL") (pin "2") (pinfunction "2_2") (pintype "passive"))
      (node (ref "U1") (pin "43") (pinfunction "P0.4_43") (pintype "bidirectional"))
    )
    (net (code "26") (name "/P0_5") (class "Default")
      (node (ref "C9") (pin "1") (pinfunction "1_1") (pintype "passive"))
      (node (ref "CRYSTAL") (pin "1") (pinfunction "1_1") (pintype "passive"))
      (node (ref "U1") (pin "44") (pinfunction "P0.5_44") (pintype "bidirectional"))
    )
    (net (code "27") (name "/S1_T") (class "Default")
      (node (ref "R4") (pin "1") (pinfunction "1_1") (pintype "passive"))
      (node (ref "U1") (pin "6") (pinfunction "P2.4_6") (pintype "bidirectional"))
      (node (ref "U2") (pin "3") (pinfunction "C_3") (pintype "bidirectional"))
    )
    (net (code "28") (name "/S2_T") (class "Default")
      (node (ref "S2_T_C2") (pin "TP") (pinfunction "TP_TP") (pintype "input"))
      (node (ref "U1") (pin "7") (pinfunction "P2.5_7") (pintype "bidirectional"))
    )
    (net (code "29") (name "/S2_T_C2") (class "Default")
      (node (ref "R6") (pin "1") (pinfunction "1_1") (pintype "passive"))
      (node (ref "S2_T_C2_C1") (pin "TP") (pinfunction "TP_TP") (pintype "input"))
      (node (ref "U3") (pin "3") (pinfunction "C_3") (pintype "bidirectional"))
    )
    (net (code "30") (name "/S3_T") (class "Default")
      (node (ref "S3_T_C3") (pin "TP") (pinfunction "TP_TP") (pintype "input"))
      (node (ref "U1") (pin "8") (pinfunction "P2.6_8") (pintype "bidirectional"))
    )
    (net (code "31") (name "/S3_T_C3") (class "Default")
      (node (ref "R8") (pin "1") (pinfunction "1_1") (pintype "passive"))
      (node (ref "S3_T_C3_C2") (pin "TP") (pinfunction "TP_TP") (pintype "input"))
      (node (ref "U4") (pin "3") (pinfunction "C_3") (pintype "bidirectional"))
    )
    (net (code "32") (name "/S4_J_C4") (class "Default")
      (node (ref "R10") (pin "1") (pinfunction "1_1") (pintype "passive"))
      (node (ref "U5") (pin "3") (pinfunction "C_3") (pintype "bidirectional"))
      (node (ref "X2") (pin "4") (pinfunction "1_4") (pintype "passive"))
    )
    (net (code "33") (name "/S4_T") (class "Default")
      (node (ref "S4_T_C4") (pin "TP") (pinfunction "TP_TP") (pintype "input"))
      (node (ref "U1") (pin "9") (pinfunction "P2.7_9") (pintype "bidirectional"))
    )
    (net (code "34") (name "/S4_T_C4") (class "Default")
      (node (ref "S4_T_C4_C2") (pin "TP") (pinfunction "TP_TP") (pintype "input"))
      (node (ref "X1") (pin "4") (pinfunction "1_4") (pintype "passive"))
    )
    (net (code "35") (name "/SAR_BY") (class "Default")
      (node (ref "C6") (pin "1") (pinfunction "1_1") (pintype "passive"))
      (node (ref "U1") (pin "1") (pinfunction "P1.7/VREF_1") (pintype "bidirectional"))
    )
    (net (code "36") (name "/SWDCLK") (class "Default")
      (node (ref "R2") (pin "2") (pinfunction "2_2") (pintype "passive"))
      (node (ref "U1") (pin "21") (pinfunction "P3.3_21") (pintype "bidirectional"))
    )
    (net (code "37") (name "/SWDIO") (class "Default")
      (node (ref "R3") (pin "2") (pinfunction "2_2") (pintype "passive"))
      (node (ref "U1") (pin "20") (pinfunction "P3.2_20") (pintype "bidirectional"))
    )
    (net (code "38") (name "/UART_RX") (class "Default")
      (node (ref "U1") (pin "37") (pinfunction "P7.0/SCB3:SCL1_37") (pintype "bidirectional"))
    )
    (net (code "39") (name "/UART_TX") (class "Default")
      (node (ref "U1") (pin "38") (pinfunction "P7.1/SCB3:SDA1_38") (pintype "bidirectional"))
    )
    (net (code "40") (name "/VCCD") (class "Default")
      (node (ref "C7") (pin "1") (pinfunction "1_1") (pintype "passive"))
      (node (ref "U1") (pin "48") (pinfunction "VCCD_48") (pintype "bidirectional"))
    )
    (net (code "41") (name "/VCC_C2") (class "Default")
      (node (ref "DINA") (pin "2") (pinfunction "2_2") (pintype "passive"))
      (node (ref "IC1") (pin "3") (pinfunction "IN_3") (pintype "input"))
      (node (ref "VCC_1_C2") (pin "TP") (pinfunction "TP_TP") (pintype "input"))
      (node (ref "VCC_2_C2") (pin "TP") (pinfunction "TP_TP") (pintype "input"))
      (node (ref "VCC_C2") (pin "TP") (pinfunction "TP_TP") (pintype "input"))
      (node (ref "VCC_C2_C3") (pin "TP") (pinfunction "TP_TP") (pintype "input"))
    )
    (net (code "42") (name "/VCC_C3") (class "Default")
      (node (ref "VCC_1_C3") (pin "TP") (pinfunction "TP_TP") (pintype "input"))
      (node (ref "VCC_2_C3") (pin "TP") (pinfunction "TP_TP") (pintype "input"))
      (node (ref "VCC_3_C3") (pin "TP") (pinfunction "TP_TP") (pintype "input"))
      (node (ref "VCC_4_C3") (pin "TP") (pinfunction "TP_TP") (pintype "input"))
      (node (ref "VCC_C3") (pin "TP") (pinfunction "TP_TP") (pintype "input"))
      (node (ref "X1") (pin "2") (pinfunction "1_2") (pintype "passive"))
    )
    (net (code "43") (name "/VCC_C4") (class "Default")
      (node (ref "VCC_1_C4") (pin "TP") (pinfunction "TP_TP") (pintype "input"))
      (node (ref "VCC_2_C4") (pin "TP") (pinfunction "TP_TP") (pintype "input"))
      (node (ref "VCC_3_C4") (pin "TP") (pinfunction "TP_TP") (pintype "input"))
      (node (ref "VCC_4_C4") (pin "TP") (pinfunction "TP_TP") (pintype "input"))
      (node (ref "X2") (pin "2") (pinfunction "1_2") (pintype "passive"))
    )
    (net (code "44") (name "/VDDA") (class "Default")
      (node (ref "U1") (pin "11") (pinfunction "VDDA1_11") (pintype "bidirectional"))
      (node (ref "U1") (pin "56") (pinfunction "VDDA2_56") (pintype "bidirectional"))
      (node (ref "VDDA_C1") (pin "TP") (pinfunction "TP_TP") (pintype "input"))
    )
    (net (code "45") (name "/VDDA2") (class "Default")
      (node (ref "L1") (pin "2") (pinfunction "2_2") (pintype "passive"))
      (node (ref "VDDA_C2") (pin "TP") (pinfunction "TP_TP") (pintype "input"))
    )
    (net (code "46") (name "/VDDD") (class "Default")
      (node (ref "U1") (pin "50") (pinfunction "VDDD_50") (pintype "bidirectional"))
      (node (ref "VDDD_C1") (pin "TP") (pinfunction "TP_TP") (pintype "input"))
    )
    (net (code "47") (name "/VDDD2") (class "Default")
      (node (ref "L4") (pin "2") (pinfunction "2_2") (pintype "passive"))
      (node (ref "VDDD_C2") (pin "TP") (pinfunction "TP_TP") (pintype "input"))
    )
    (net (code "48") (name "/VDDIO") (class "Default")
      (node (ref "U1") (pin "26") (pinfunction "VDDIO_26") (pintype "bidirectional"))
      (node (ref "VDDIO_C1") (pin "TP") (pinfunction "TP_TP") (pintype "input"))
    )
    (net (code "49") (name "/VDDIO2") (class "Default")
      (node (ref "R15") (pin "2") (pinfunction "2_2") (pintype "passive"))
      (node (ref "VDDIO_C2") (pin "TP") (pinfunction "TP_TP") (pintype "input"))
    )
    (net (code "50") (name "/XRES") (class "Default")
      (node (ref "C10") (pin "1") (pinfunction "1_1") (pintype "passive"))
      (node (ref "R1") (pin "2") (pinfunction "2_2") (pintype "passive"))
      (node (ref "R14") (pin "2") (pinfunction "2_2") (pintype "passive"))
      (node (ref "U1") (pin "47") (pinfunction "XRES_47") (pintype "bidirectional"))
    )
    (net (code "51") (name "GND1") (class "Default")
      (node (ref "C10") (pin "2") (pinfunction "2_2") (pintype "passive"))
      (node (ref "C4") (pin "2") (pinfunction "2_2") (pintype "passive"))
      (node (ref "C5") (pin "2") (pinfunction "2_2") (pintype "passive"))
      (node (ref "C6") (pin "2") (pinfunction "2_2") (pintype "passive"))
      (node (ref "C7") (pin "2") (pinfunction "2_2") (pintype "passive"))
      (node (ref "C8") (pin "2") (pinfunction "2_2") (pintype "passive"))
      (node (ref "C9") (pin "2") (pinfunction "2_2") (pintype "passive"))
      (node (ref "CN1") (pin "D-") (pinfunction "D-_D-") (pintype "bidirectional"))
      (node (ref "GND_1_C1") (pin "TP") (pinfunction "TP_TP") (pintype "input"))
      (node (ref "GND_2_C1") (pin "TP") (pinfunction "TP_TP") (pintype "input"))
      (node (ref "GND_3_C1") (pin "TP") (pinfunction "TP_TP") (pintype "input"))
      (node (ref "GND_4_C1") (pin "TP") (pinfunction "TP_TP") (pintype "input"))
      (node (ref "GND_C1") (pin "TP") (pinfunction "TP_TP") (pintype "input"))
      (node (ref "R12") (pin "1") (pinfunction "1_1") (pintype "passive"))
      (node (ref "R13") (pin "1") (pinfunction "1_1") (pintype "passive"))
      (node (ref "R17") (pin "2") (pinfunction "2_2") (pintype "passive"))
      (node (ref "R18") (pin "1") (pinfunction "1_1") (pintype "passive"))
      (node (ref "R19") (pin "2") (pinfunction "2_2") (pintype "passive"))
      (node (ref "U$1") (pin "2") (pinfunction "GND_2") (pintype "power_in"))
      (node (ref "U1") (pin "10") (pinfunction "VSSA1_10") (pintype "bidirectional"))
      (node (ref "U1") (pin "17") (pinfunction "VSSIO_17") (pintype "bidirectional"))
      (node (ref "U1") (pin "49") (pinfunction "VSSD_49") (pintype "bidirectional"))
      (node (ref "U1") (pin "57") (pinfunction "VSSA2_57") (pintype "bidirectional"))
      (node (ref "U2") (pin "4") (pinfunction "E_4") (pintype "bidirectional"))
    )
    (net (code "52") (name "GND2") (class "Default")
      (node (ref "DINA") (pin "3") (pinfunction "3_3") (pintype "passive"))
      (node (ref "GND_1_C2") (pin "TP") (pinfunction "TP_TP") (pintype "input"))
      (node (ref "GND_2_C2") (pin "TP") (pinfunction "TP_TP") (pintype "input"))
      (node (ref "GND_C2") (pin "TP") (pinfunction "TP_TP") (pintype "input"))
      (node (ref "GND_C2_C3") (pin "TP") (pinfunction "TP_TP") (pintype "input"))
      (node (ref "IC1") (pin "1") (pinfunction "ADJ_1") (pintype "input"))
      (node (ref "R20") (pin "2") (pinfunction "2_2") (pintype "passive"))
      (node (ref "R23") (pin "2") (pinfunction "2_2") (pintype "passive"))
      (node (ref "R5") (pin "1") (pinfunction "1_1") (pintype "passive"))
      (node (ref "U3") (pin "4") (pinfunction "E_4") (pintype "bidirectional"))
    )
    (net (code "53") (name "GND3") (class "Default")
      (node (ref "GND_1_C3") (pin "TP") (pinfunction "TP_TP") (pintype "input"))
      (node (ref "GND_2_C3") (pin "TP") (pinfunction "TP_TP") (pintype "input"))
      (node (ref "GND_3_C3") (pin "TP") (pinfunction "TP_TP") (pintype "input"))
      (node (ref "GND_4_C3") (pin "TP") (pinfunction "TP_TP") (pintype "input"))
      (node (ref "GND_C3") (pin "TP") (pinfunction "TP_TP") (pintype "input"))
      (node (ref "R21") (pin "2") (pinfunction "2_2") (pintype "passive"))
      (node (ref "R7") (pin "1") (pinfunction "1_1") (pintype "passive"))
      (node (ref "U4") (pin "4") (pinfunction "E_4") (pintype "bidirectional"))
      (node (ref "X1") (pin "3") (pinfunction "1_3") (pintype "passive"))
    )
    (net (code "54") (name "GND4") (class "Default")
      (node (ref "GND_1_C4") (pin "TP") (pinfunction "TP_TP") (pintype "input"))
      (node (ref "GND_2_C4") (pin "TP") (pinfunction "TP_TP") (pintype "input"))
      (node (ref "GND_3_C4") (pin "TP") (pinfunction "TP_TP") (pintype "input"))
      (node (ref "GND_4_C4") (pin "TP") (pinfunction "TP_TP") (pintype "input"))
      (node (ref "R22") (pin "2") (pinfunction "2_2") (pintype "passive"))
      (node (ref "R9") (pin "1") (pinfunction "1_1") (pintype "passive"))
      (node (ref "U5") (pin "4") (pinfunction "E_4") (pintype "bidirectional"))
      (node (ref "X2") (pin "3") (pinfunction "1_3") (pintype "passive"))
    )
    (net (code "55") (name "Net-(CANH_1_C2-PadTP)") (class "Default")
      (node (ref "CANH_1_C2") (pin "TP") (pinfunction "TP_TP") (pintype "input"))
      (node (ref "CANH_2_C2") (pin "TP") (pinfunction "TP_TP") (pintype "input"))
      (node (ref "CANH_C2") (pin "TP") (pinfunction "TP_TP") (pintype "input"))
      (node (ref "CANH_C2_C3") (pin "TP") (pinfunction "TP_TP") (pintype "input"))
    )
    (net (code "56") (name "Net-(CANL_1_C2-PadTP)") (class "Default")
      (node (ref "CANL_1_C2") (pin "TP") (pinfunction "TP_TP") (pintype "input"))
      (node (ref "CANL_2_C2") (pin "TP") (pinfunction "TP_TP") (pintype "input"))
      (node (ref "CANL_C2") (pin "TP") (pinfunction "TP_TP") (pintype "input"))
      (node (ref "CANL_C2_C3") (pin "TP") (pinfunction "TP_TP") (pintype "input"))
    )
    (net (code "57") (name "Net-(CN1-PadD+)") (class "Default")
      (node (ref "CN1") (pin "D+") (pinfunction "D+_D+") (pintype "bidirectional"))
      (node (ref "R1") (pin "1") (pinfunction "1_1") (pintype "passive"))
    )
    (net (code "58") (name "Net-(CN1-PadGND)") (class "Default")
      (node (ref "CN1") (pin "GND") (pinfunction "GND_GND") (pintype "power_in"))
      (node (ref "R3") (pin "1") (pinfunction "1_1") (pintype "passive"))
    )
    (net (code "59") (name "Net-(CN1-PadID)") (class "Default")
      (node (ref "CN1") (pin "ID") (pinfunction "ID_ID") (pintype "bidirectional"))
      (node (ref "R2") (pin "1") (pinfunction "1_1") (pintype "passive"))
    )
    (net (code "60") (name "Net-(DINA-Pad1)") (class "Default")
      (node (ref "DINA") (pin "1") (pinfunction "1_1") (pintype "passive"))
      (node (ref "DN_C2") (pin "TP") (pinfunction "TP_TP") (pintype "input"))
    )
    (net (code "61") (name "Net-(DN_C1-PadTP)") (class "Default")
      (node (ref "DN_C1") (pin "TP") (pinfunction "TP_TP") (pintype "input"))
      (node (ref "S1") (pin "2") (pinfunction "2_2") (pintype "passive"))
    )
    (net (code "62") (name "Net-(LED1-PadC)") (class "Default")
      (node (ref "LED1") (pin "C") (pinfunction "C_C") (pintype "passive"))
      (node (ref "R19") (pin "1") (pinfunction "1_1") (pintype "passive"))
    )
    (net (code "63") (name "Net-(LED2-PadC)") (class "Default")
      (node (ref "LED2") (pin "C") (pinfunction "C_C") (pintype "passive"))
      (node (ref "R20") (pin "1") (pinfunction "1_1") (pintype "passive"))
    )
    (net (code "64") (name "Net-(LED3-PadC)") (class "Default")
      (node (ref "LED3") (pin "C") (pinfunction "C_C") (pintype "passive"))
      (node (ref "R21") (pin "1") (pinfunction "1_1") (pintype "passive"))
    )
    (net (code "65") (name "Net-(LED4-PadC)") (class "Default")
      (node (ref "LED4") (pin "C") (pinfunction "C_C") (pintype "passive"))
      (node (ref "R22") (pin "1") (pinfunction "1_1") (pintype "passive"))
    )
    (net (code "66") (name "Net-(LED5-PadC)") (class "Default")
      (node (ref "LED5") (pin "C") (pinfunction "C_C") (pintype "passive"))
      (node (ref "R23") (pin "1") (pinfunction "1_1") (pintype "passive"))
    )
    (net (code "67") (name "Net-(L_C1_C3-PadTP)") (class "Default")
      (node (ref "L_C1_C3") (pin "TP") (pinfunction "TP_TP") (pintype "input"))
      (node (ref "L_C3_C2") (pin "TP") (pinfunction "TP_TP") (pintype "input"))
    )
    (net (code "68") (name "Net-(L_C1_C4-PadTP)") (class "Default")
      (node (ref "L_C1_C4") (pin "TP") (pinfunction "TP_TP") (pintype "input"))
      (node (ref "L_C4_C1") (pin "TP") (pinfunction "TP_TP") (pintype "input"))
    )
    (net (code "69") (name "Net-(R11-Pad2)") (class "Default")
      (node (ref "R11") (pin "2") (pinfunction "2_2") (pintype "passive"))
      (node (ref "R13") (pin "2") (pinfunction "2_2") (pintype "passive"))
    )
    (net (code "70") (name "Net-(S3_T_C1_C3-PadTP)") (class "Default")
      (node (ref "S3_T_C1_C3") (pin "TP") (pinfunction "TP_TP") (pintype "input"))
      (node (ref "S3_T_C3_C1") (pin "TP") (pinfunction "TP_TP") (pintype "input"))
    )
    (net (code "71") (name "Net-(S4_T_C1_C4-PadTP)") (class "Default")
      (node (ref "S4_T_C1_C4") (pin "TP") (pinfunction "TP_TP") (pintype "input"))
      (node (ref "S4_T_C4_C1") (pin "TP") (pinfunction "TP_TP") (pintype "input"))
    )
    (net (code "72") (name "Net-(U$1-CANH)") (class "Default")
      (node (ref "R16") (pin "2") (pinfunction "2_2") (pintype "passive"))
      (node (ref "S1") (pin "4") (pinfunction "4_4") (pintype "passive"))
      (node (ref "U$1") (pin "7") (pinfunction "CANH_7") (pintype "bidirectional"))
    )
    (net (code "73") (name "Net-(U$1-RS)") (class "Default")
      (node (ref "R17") (pin "1") (pinfunction "1_1") (pintype "passive"))
      (node (ref "U$1") (pin "8") (pinfunction "RS_8") (pintype "bidirectional"))
    )
    (net (code "74") (name "Net-(U2-K)") (class "Default")
      (node (ref "R12") (pin "2") (pinfunction "2_2") (pintype "passive"))
      (node (ref "U2") (pin "2") (pinfunction "K_2") (pintype "bidirectional"))
    )
    (net (code "75") (name "Net-(U3-K)") (class "Default")
      (node (ref "R5") (pin "2") (pinfunction "2_2") (pintype "passive"))
      (node (ref "U3") (pin "2") (pinfunction "K_2") (pintype "bidirectional"))
    )
    (net (code "76") (name "Net-(U4-K)") (class "Default")
      (node (ref "R7") (pin "2") (pinfunction "2_2") (pintype "passive"))
      (node (ref "U4") (pin "2") (pinfunction "K_2") (pintype "bidirectional"))
    )
    (net (code "77") (name "Net-(U5-K)") (class "Default")
      (node (ref "R9") (pin "2") (pinfunction "2_2") (pintype "passive"))
      (node (ref "U5") (pin "2") (pinfunction "K_2") (pintype "bidirectional"))
    )
    (net (code "78") (name "Net-(VCC_1_C1-PadTP)") (class "Default")
      (node (ref "VCC_1_C1") (pin "TP") (pinfunction "TP_TP") (pintype "input"))
      (node (ref "VCC_2_C1") (pin "TP") (pinfunction "TP_TP") (pintype "input"))
      (node (ref "VCC_3_C1") (pin "TP") (pinfunction "TP_TP") (pintype "input"))
      (node (ref "VCC_4_C1") (pin "TP") (pinfunction "TP_TP") (pintype "input"))
      (node (ref "VCC_C1") (pin "TP") (pinfunction "TP_TP") (pintype "input"))
    )
    (net (code "79") (name "unconnected-(MECH_LINK_1-PadTP)") (class "Default")
      (node (ref "MECH_LINK_1") (pin "TP") (pinfunction "TP_TP") (pintype "input"))
    )
    (net (code "80") (name "unconnected-(MECH_LINK_2-PadTP)") (class "Default")
      (node (ref "MECH_LINK_2") (pin "TP") (pinfunction "TP_TP") (pintype "input"))
    )
    (net (code "81") (name "unconnected-(MECH_LINK_3-PadTP)") (class "Default")
      (node (ref "MECH_LINK_3") (pin "TP") (pinfunction "TP_TP") (pintype "input"))
    )
    (net (code "82") (name "unconnected-(MECH_LINK_4-PadTP)") (class "Default")
      (node (ref "MECH_LINK_4") (pin "TP") (pinfunction "TP_TP") (pintype "input"))
    )
    (net (code "83") (name "unconnected-(MECH_LINK_5-PadTP)") (class "Default")
      (node (ref "MECH_LINK_5") (pin "TP") (pinfunction "TP_TP") (pintype "input"))
    )
    (net (code "84") (name "unconnected-(MECH_LINK_6-PadTP)") (class "Default")
      (node (ref "MECH_LINK_6") (pin "TP") (pinfunction "TP_TP") (pintype "input"))
    )
    (net (code "85") (name "unconnected-(MECH_LINK_7-PadTP)") (class "Default")
      (node (ref "MECH_LINK_7") (pin "TP") (pinfunction "TP_TP") (pintype "input"))
    )
    (net (code "86") (name "unconnected-(MECH_LINK_8-PadTP)") (class "Default")
      (node (ref "MECH_LINK_8") (pin "TP") (pinfunction "TP_TP") (pintype "input"))
    )
    (net (code "87") (name "unconnected-(MECH_LINK_9-PadTP)") (class "Default")
      (node (ref "MECH_LINK_9") (pin "TP") (pinfunction "TP_TP") (pintype "input"))
    )
    (net (code "88") (name "unconnected-(MECH_LINK_11-PadTP)") (class "Default")
      (node (ref "MECH_LINK_11") (pin "TP") (pinfunction "TP_TP") (pintype "input"))
    )
    (net (code "89") (name "unconnected-(MECH_LINK_12-PadTP)") (class "Default")
      (node (ref "MECH_LINK_12") (pin "TP") (pinfunction "TP_TP") (pintype "input"))
    )
    (net (code "90") (name "unconnected-(MECH_LINK_13-PadTP)") (class "Default")
      (node (ref "MECH_LINK_13") (pin "TP") (pinfunction "TP_TP") (pintype "input"))
    )
    (net (code "91") (name "unconnected-(MECH_LINK_14-PadTP)") (class "Default")
      (node (ref "MECH_LINK_14") (pin "TP") (pinfunction "TP_TP") (pintype "input"))
    )
    (net (code "92") (name "unconnected-(MECH_LINK_16-PadTP)") (class "Default")
      (node (ref "MECH_LINK_16") (pin "TP") (pinfunction "TP_TP") (pintype "input"))
    )
    (net (code "93") (name "unconnected-(U$1-VREF-Pad5)") (class "Default")
      (node (ref "U$1") (pin "5") (pinfunction "VREF_5") (pintype "bidirectional"))
    )
    (net (code "94") (name "unconnected-(U1-NC1-Pad34)") (class "Default")
      (node (ref "U1") (pin "34") (pinfunction "NC1_34") (pintype "bidirectional"))
    )
    (net (code "95") (name "unconnected-(U1-NC2-Pad35)") (class "Default")
      (node (ref "U1") (pin "35") (pinfunction "NC2_35") (pintype "bidirectional"))
    )
    (net (code "96") (name "unconnected-(U1-NC3-Pad36)") (class "Default")
      (node (ref "U1") (pin "36") (pinfunction "NC3_36") (pintype "bidirectional"))
    )
    (net (code "97") (name "unconnected-(U1-P0.0{slash}CAN1RX-Pad39)") (class "Default")
      (node (ref "U1") (pin "39") (pinfunction "P0.0/CAN1RX_39") (pintype "bidirectional"))
    )
    (net (code "98") (name "unconnected-(U1-P0.2-Pad41)") (class "Default")
      (node (ref "U1") (pin "41") (pinfunction "P0.2_41") (pintype "bidirectional"))
    )
    (net (code "99") (name "unconnected-(U1-P0.3-Pad42)") (class "Default")
      (node (ref "U1") (pin "42") (pinfunction "P0.3_42") (pintype "bidirectional"))
    )
    (net (code "100") (name "unconnected-(U1-P0.6-Pad45)") (class "Default")
      (node (ref "U1") (pin "45") (pinfunction "P0.6_45") (pintype "bidirectional"))
    )
    (net (code "101") (name "unconnected-(U1-P0.7{slash}CAN1TX_EN-Pad46)") (class "Default")
      (node (ref "U1") (pin "46") (pinfunction "P0.7/CAN1TX_EN_46") (pintype "bidirectional"))
    )
    (net (code "102") (name "unconnected-(U1-P1.0-Pad58)") (class "Default")
      (node (ref "U1") (pin "58") (pinfunction "P1.0_58") (pintype "bidirectional"))
    )
    (net (code "103") (name "unconnected-(U1-P1.1-Pad59)") (class "Default")
      (node (ref "U1") (pin "59") (pinfunction "P1.1_59") (pintype "bidirectional"))
    )
    (net (code "104") (name "unconnected-(U1-P1.2-Pad60)") (class "Default")
      (node (ref "U1") (pin "60") (pinfunction "P1.2_60") (pintype "bidirectional"))
    )
    (net (code "105") (name "unconnected-(U1-P1.3-Pad61)") (class "Default")
      (node (ref "U1") (pin "61") (pinfunction "P1.3_61") (pintype "bidirectional"))
    )
    (net (code "106") (name "unconnected-(U1-P1.6-Pad64)") (class "Default")
      (node (ref "U1") (pin "64") (pinfunction "P1.6_64") (pintype "bidirectional"))
    )
    (net (code "107") (name "unconnected-(U1-P3.0{slash}SCB1:RX-Pad18)") (class "Default")
      (node (ref "U1") (pin "18") (pinfunction "P3.0/SCB1:RX_18") (pintype "bidirectional"))
    )
    (net (code "108") (name "unconnected-(U1-P3.1{slash}SCB1:TX-Pad19)") (class "Default")
      (node (ref "U1") (pin "19") (pinfunction "P3.1/SCB1:TX_19") (pintype "bidirectional"))
    )
    (net (code "109") (name "unconnected-(U1-P3.4-Pad22)") (class "Default")
      (node (ref "U1") (pin "22") (pinfunction "P3.4_22") (pintype "bidirectional"))
    )
    (net (code "110") (name "unconnected-(U1-P3.5-Pad23)") (class "Default")
      (node (ref "U1") (pin "23") (pinfunction "P3.5_23") (pintype "bidirectional"))
    )
    (net (code "111") (name "unconnected-(U1-P3.6-Pad24)") (class "Default")
      (node (ref "U1") (pin "24") (pinfunction "P3.6_24") (pintype "bidirectional"))
    )
    (net (code "112") (name "unconnected-(U1-P3.7-Pad25)") (class "Default")
      (node (ref "U1") (pin "25") (pinfunction "P3.7_25") (pintype "bidirectional"))
    )
    (net (code "113") (name "unconnected-(U1-P4.0{slash}SCB0:SCL1-Pad27)") (class "Default")
      (node (ref "U1") (pin "27") (pinfunction "P4.0/SCB0:SCL1_27") (pintype "bidirectional"))
    )
    (net (code "114") (name "unconnected-(U1-P4.1{slash}SCB0:SDA1-Pad28)") (class "Default")
      (node (ref "U1") (pin "28") (pinfunction "P4.1/SCB0:SDA1_28") (pintype "bidirectional"))
    )
    (net (code "115") (name "unconnected-(U1-P4.4-Pad31)") (class "Default")
      (node (ref "U1") (pin "31") (pinfunction "P4.4_31") (pintype "bidirectional"))
    )
    (net (code "116") (name "unconnected-(U1-P4.5-Pad32)") (class "Default")
      (node (ref "U1") (pin "32") (pinfunction "P4.5_32") (pintype "bidirectional"))
    )
    (net (code "117") (name "unconnected-(U1-P4.6-Pad33)") (class "Default")
      (node (ref "U1") (pin "33") (pinfunction "P4.6_33") (pintype "bidirectional"))
    )
    (net (code "118") (name "unconnected-(U1-P5.0-Pad51)") (class "Default")
      (node (ref "U1") (pin "51") (pinfunction "P5.0_51") (pintype "bidirectional"))
    )
    (net (code "119") (name "unconnected-(U1-P5.1-Pad52)") (class "Default")
      (node (ref "U1") (pin "52") (pinfunction "P5.1_52") (pintype "bidirectional"))
    )
    (net (code "120") (name "unconnected-(U1-P5.2-Pad53)") (class "Default")
      (node (ref "U1") (pin "53") (pinfunction "P5.2_53") (pintype "bidirectional"))
    )
    (net (code "121") (name "unconnected-(U1-P5.3-Pad54)") (class "Default")
      (node (ref "U1") (pin "54") (pinfunction "P5.3_54") (pintype "bidirectional"))
    )
    (net (code "122") (name "unconnected-(U1-P5.5-Pad55)") (class "Default")
      (node (ref "U1") (pin "55") (pinfunction "P5.5_55") (pintype "bidirectional"))
    )
    (net (code "123") (name "unconnected-(U1-P6.0{slash}CAN0TX_EN-Pad12)") (class "Default")
      (node (ref "U1") (pin "12") (pinfunction "P6.0/CAN0TX_EN_12") (pintype "bidirectional"))
    )
    (net (code "124") (name "unconnected-(U1-P6.4-Pad15)") (class "Default")
      (node (ref "U1") (pin "15") (pinfunction "P6.4_15") (pintype "bidirectional"))
    )
    (net (code "125") (name "unconnected-(U1-P6.5-Pad16)") (class "Default")
      (node (ref "U1") (pin "16") (pinfunction "P6.5_16") (pintype "bidirectional"))
    )
    (net (code "126") (name "unconnected-(X1B-1-Pad10)") (class "Default")
      (node (ref "X1") (pin "10") (pinfunction "1_10") (pintype "passive"))
    )
    (net (code "127") (name "unconnected-(X1I-1-Pad8)") (class "Default")
      (node (ref "X1") (pin "8") (pinfunction "1_8") (pintype "passive"))
    )
    (net (code "128") (name "unconnected-(X1J-1-Pad9)") (class "Default")
      (node (ref "X1") (pin "9") (pinfunction "1_9") (pintype "passive"))
    )
    (net (code "129") (name "unconnected-(X2B-1-Pad10)") (class "Default")
      (node (ref "X2") (pin "10") (pinfunction "1_10") (pintype "passive"))
    )
    (net (code "130") (name "unconnected-(X2I-1-Pad8)") (class "Default")
      (node (ref "X2") (pin "8") (pinfunction "1_8") (pintype "passive"))
    )
    (net (code "131") (name "unconnected-(X2J-1-Pad9)") (class "Default")
      (node (ref "X2") (pin "9") (pinfunction "1_9") (pintype "passive"))
    )
  )
)
